# eGAN-FET-module_Driver.net
KiCad netlist of a schematic drawn in Altium Designer
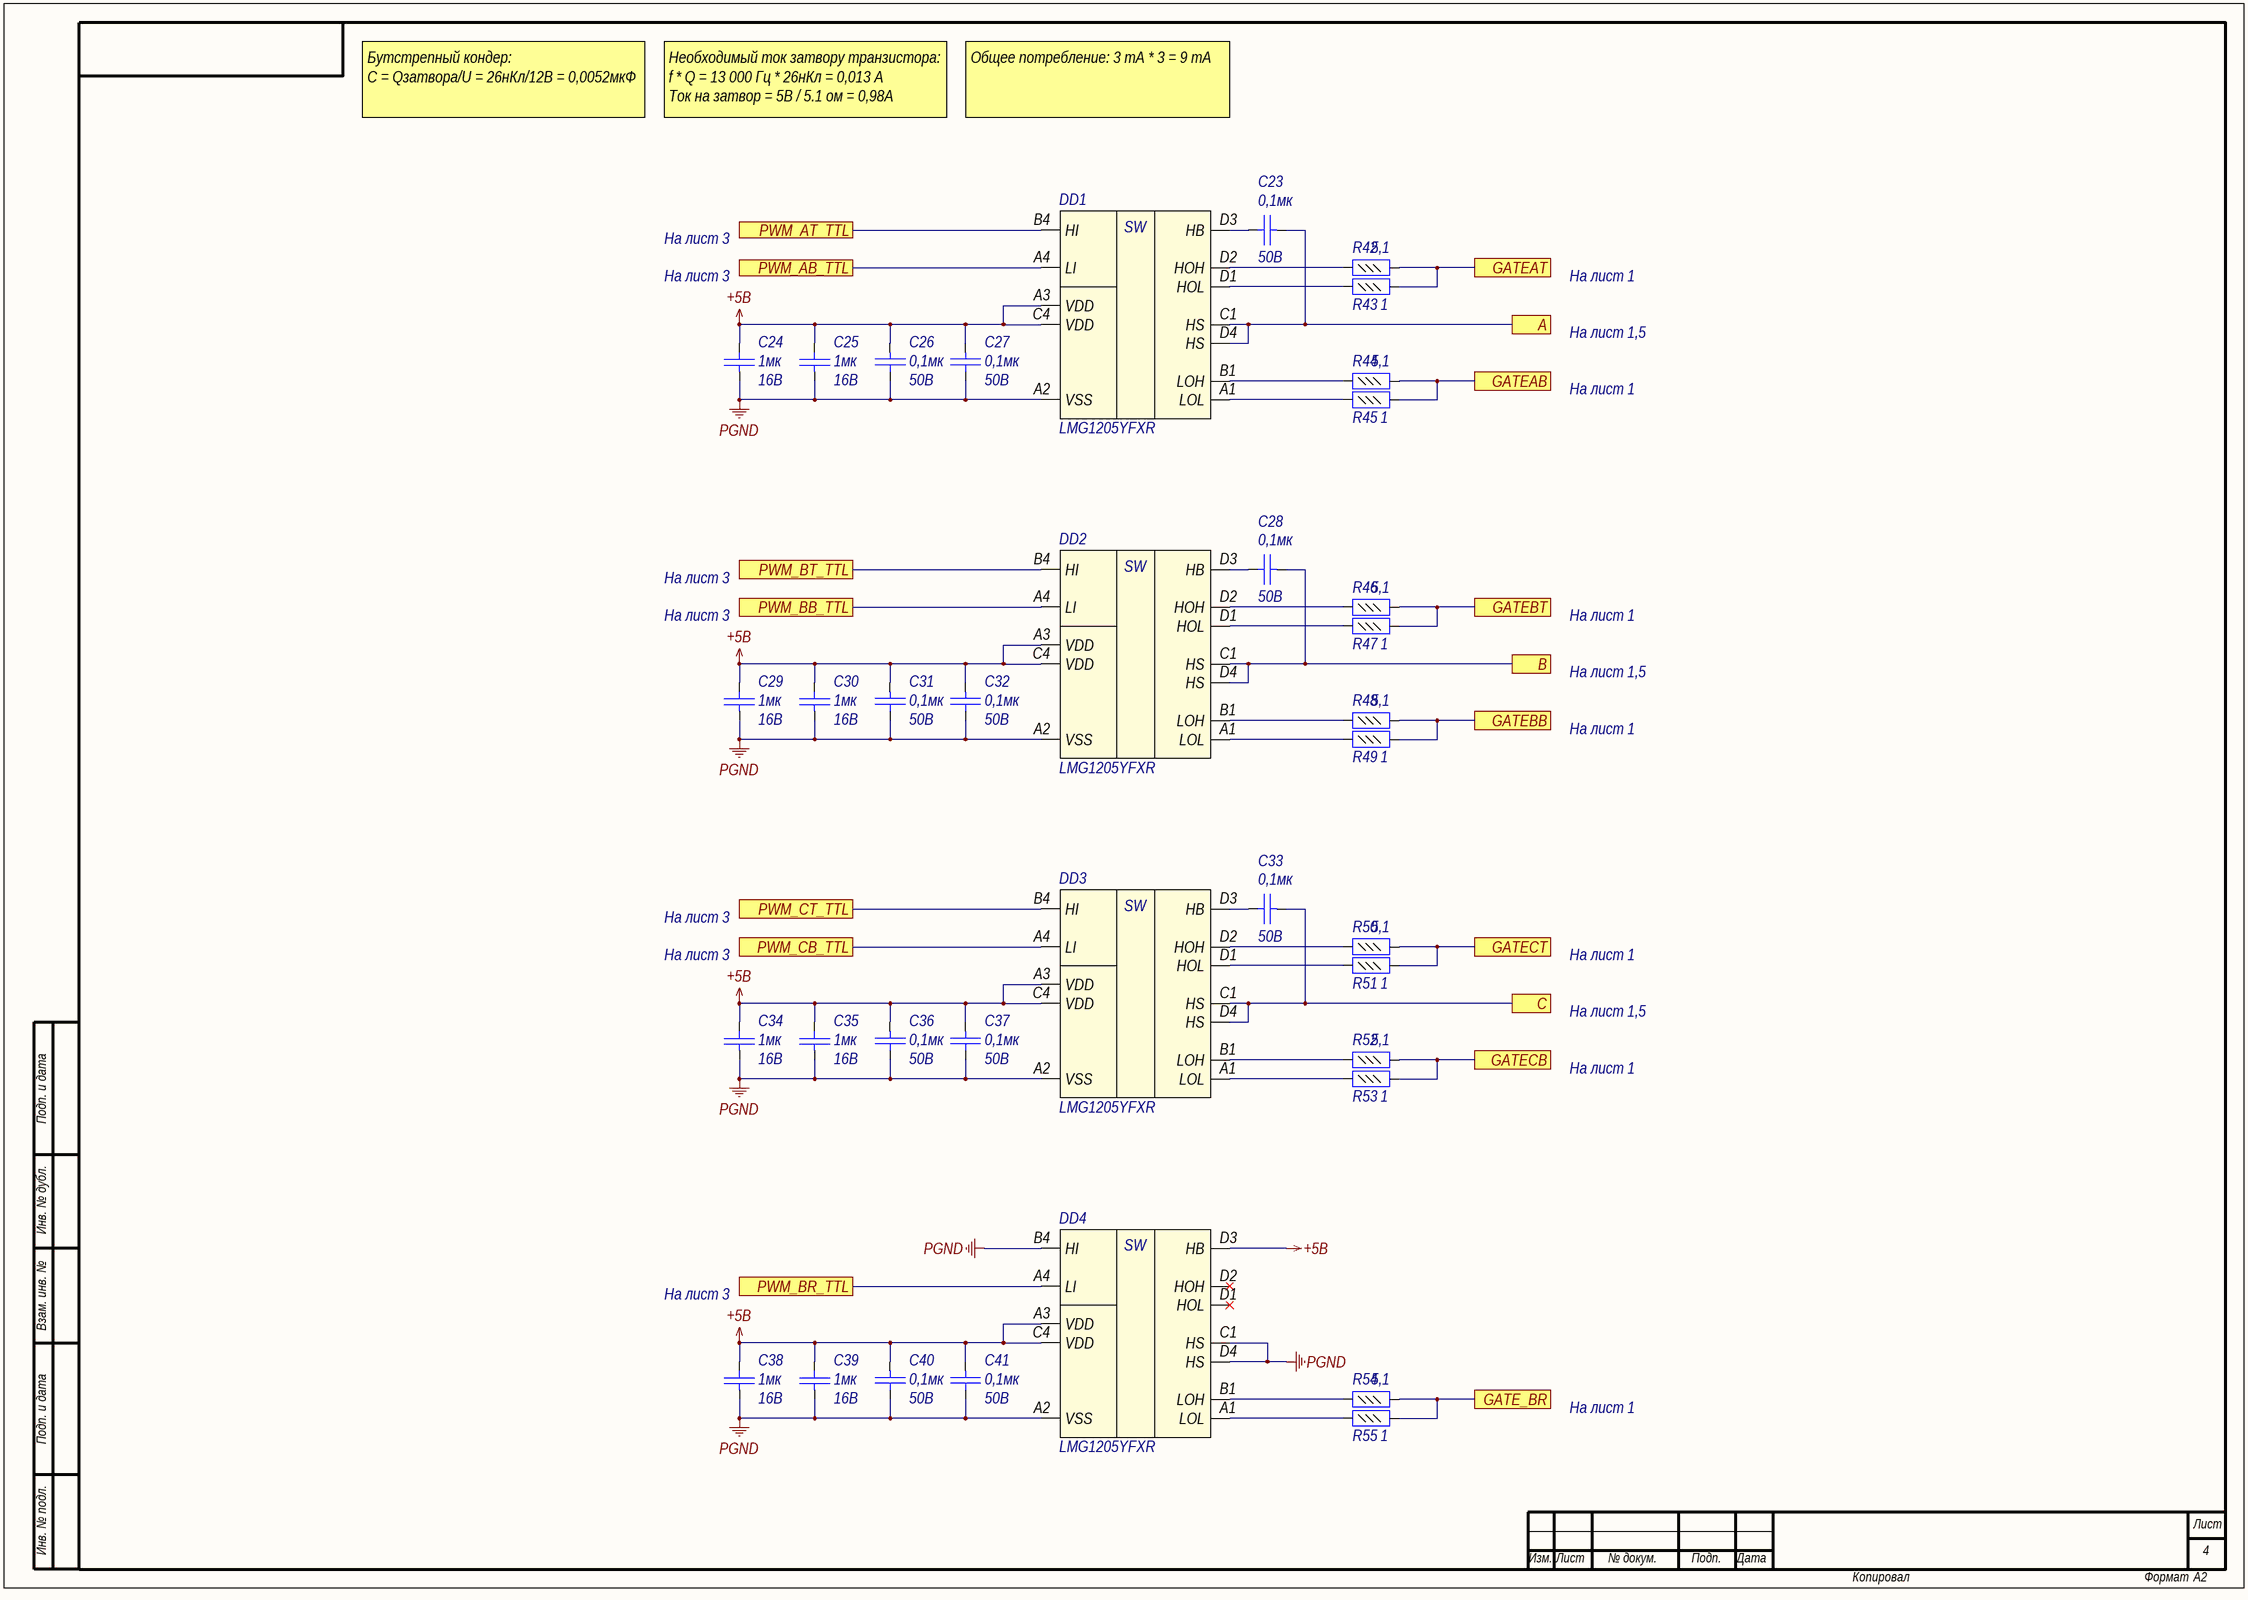
[diagram p0: eGAN-FET-module_Driver.SchDoc]

(export (version "E")
  (design (tool "Eeschema 10.0.6"))
  (components
    (comp (ref "C23")
      (value "0,1мк")
      (footprint "C0402")
      (description "Конденсатор")
      (fields
        (field (name "VOLTAGE") "50В")
        (field (name "PART NUMBER") "GRM155R71H104KE14D")
        (field (name "Comment") "Capacitor")
      )
      (libsource (lib "") (part "Capacitor_1"))
    )
    (comp (ref "C24")
      (value "1мк")
      (footprint "C0402")
      (description "Конденсатор")
      (fields (field (name "VOLTAGE") "16B") (field (name "PART NUMBER") "EMK105BJ105KV-F"))
      (libsource (lib "MOP44") (part "Capacitor"))
    )
    (comp (ref "C25")
      (value "1мк")
      (footprint "C0402")
      (description "Конденсатор")
      (fields (field (name "VOLTAGE") "16B") (field (name "PART NUMBER") "EMK105BJ105KV-F"))
      (libsource (lib "MOP44") (part "Capacitor"))
    )
    (comp (ref "C26")
      (value "0,1мк")
      (footprint "C0402")
      (description "Конденсатор")
      (fields
        (field (name "VOLTAGE") "50В")
        (field (name "PART NUMBER") "GRM155R71H104KE14D")
        (field (name "Comment") "Capacitor")
      )
      (libsource (lib "") (part "Capacitor_1"))
    )
    (comp (ref "C27")
      (value "0,1мк")
      (footprint "C0402")
      (description "Конденсатор")
      (fields
        (field (name "VOLTAGE") "50В")
        (field (name "PART NUMBER") "GRM155R71H104KE14D")
        (field (name "Comment") "Capacitor")
      )
      (libsource (lib "") (part "Capacitor_1"))
    )
    (comp (ref "C28")
      (value "0,1мк")
      (footprint "C0402")
      (description "Конденсатор")
      (fields
        (field (name "VOLTAGE") "50В")
        (field (name "PART NUMBER") "GRM155R71H104KE14D")
        (field (name "Comment") "Capacitor")
      )
      (libsource (lib "") (part "Capacitor_1"))
    )
    (comp (ref "C29")
      (value "1мк")
      (footprint "C0402")
      (description "Конденсатор")
      (fields (field (name "VOLTAGE") "16B") (field (name "PART NUMBER") "EMK105BJ105KV-F"))
      (libsource (lib "MOP44") (part "Capacitor"))
    )
    (comp (ref "C30")
      (value "1мк")
      (footprint "C0402")
      (description "Конденсатор")
      (fields (field (name "VOLTAGE") "16B") (field (name "PART NUMBER") "EMK105BJ105KV-F"))
      (libsource (lib "MOP44") (part "Capacitor"))
    )
    (comp (ref "C31")
      (value "0,1мк")
      (footprint "C0402")
      (description "Конденсатор")
      (fields
        (field (name "VOLTAGE") "50В")
        (field (name "PART NUMBER") "GRM155R71H104KE14D")
        (field (name "Comment") "Capacitor")
      )
      (libsource (lib "") (part "Capacitor_1"))
    )
    (comp (ref "C32")
      (value "0,1мк")
      (footprint "C0402")
      (description "Конденсатор")
      (fields
        (field (name "VOLTAGE") "50В")
        (field (name "PART NUMBER") "GRM155R71H104KE14D")
        (field (name "Comment") "Capacitor")
      )
      (libsource (lib "") (part "Capacitor_1"))
    )
    (comp (ref "C33")
      (value "0,1мк")
      (footprint "C0402")
      (description "Конденсатор")
      (fields
        (field (name "VOLTAGE") "50В")
        (field (name "PART NUMBER") "GRM155R71H104KE14D")
        (field (name "Comment") "Capacitor")
      )
      (libsource (lib "") (part "Capacitor_1"))
    )
    (comp (ref "C34")
      (value "1мк")
      (footprint "C0402")
      (description "Конденсатор")
      (fields (field (name "VOLTAGE") "16B") (field (name "PART NUMBER") "EMK105BJ105KV-F"))
      (libsource (lib "MOP44") (part "Capacitor"))
    )
    (comp (ref "C35")
      (value "1мк")
      (footprint "C0402")
      (description "Конденсатор")
      (fields (field (name "VOLTAGE") "16B") (field (name "PART NUMBER") "EMK105BJ105KV-F"))
      (libsource (lib "MOP44") (part "Capacitor"))
    )
    (comp (ref "C36")
      (value "0,1мк")
      (footprint "C0402")
      (description "Конденсатор")
      (fields
        (field (name "VOLTAGE") "50В")
        (field (name "PART NUMBER") "GRM155R71H104KE14D")
        (field (name "Comment") "Capacitor")
      )
      (libsource (lib "") (part "Capacitor_1"))
    )
    (comp (ref "C37")
      (value "0,1мк")
      (footprint "C0402")
      (description "Конденсатор")
      (fields
        (field (name "VOLTAGE") "50В")
        (field (name "PART NUMBER") "GRM155R71H104KE14D")
        (field (name "Comment") "Capacitor")
      )
      (libsource (lib "") (part "Capacitor_1"))
    )
    (comp (ref "C38")
      (value "1мк")
      (footprint "C0402")
      (description "Конденсатор")
      (fields (field (name "VOLTAGE") "16B") (field (name "PART NUMBER") "EMK105BJ105KV-F"))
      (libsource (lib "MOP44") (part "Capacitor"))
    )
    (comp (ref "C39")
      (value "1мк")
      (footprint "C0402")
      (description "Конденсатор")
      (fields (field (name "VOLTAGE") "16B") (field (name "PART NUMBER") "EMK105BJ105KV-F"))
      (libsource (lib "MOP44") (part "Capacitor"))
    )
    (comp (ref "C40")
      (value "0,1мк")
      (footprint "C0402")
      (description "Конденсатор")
      (fields
        (field (name "VOLTAGE") "50В")
        (field (name "PART NUMBER") "GRM155R71H104KE14D")
        (field (name "Comment") "Capacitor")
      )
      (libsource (lib "") (part "Capacitor_1"))
    )
    (comp (ref "C41")
      (value "0,1мк")
      (footprint "C0402")
      (description "Конденсатор")
      (fields
        (field (name "VOLTAGE") "50В")
        (field (name "PART NUMBER") "GRM155R71H104KE14D")
        (field (name "Comment") "Capacitor")
      )
      (libsource (lib "") (part "Capacitor_1"))
    )
    (comp (ref "DD1")
      (value "LMG1205YFXR")
      (footprint "DSBGA12")
      (description "80-V, 1.2-A to 5-A, Half Bridge GaN Driver with Integrated Bootstrap Diode")
      (libsource (lib "MOP44") (part "LMG1205"))
    )
    (comp (ref "DD2")
      (value "LMG1205YFXR")
      (footprint "DSBGA12")
      (description "80-V, 1.2-A to 5-A, Half Bridge GaN Driver with Integrated Bootstrap Diode")
      (libsource (lib "MOP44") (part "LMG1205"))
    )
    (comp (ref "DD3")
      (value "LMG1205YFXR")
      (footprint "DSBGA12")
      (description "80-V, 1.2-A to 5-A, Half Bridge GaN Driver with Integrated Bootstrap Diode")
      (libsource (lib "MOP44") (part "LMG1205"))
    )
    (comp (ref "DD4")
      (value "LMG1205YFXR")
      (footprint "DSBGA12")
      (description "80-V, 1.2-A to 5-A, Half Bridge GaN Driver with Integrated Bootstrap Diode")
      (libsource (lib "MOP44") (part "LMG1205"))
    )
    (comp (ref "R42")
      (value "5,1")
      (footprint "R0402")
      (description "Резистор")
      (fields (field (name "PART NUMBER") "RC0402FR-075R1L") (field (name "POWER") "0,062Вт"))
      (libsource (lib "MOP44") (part "Resistor_0,062Вт"))
    )
    (comp (ref "R43")
      (value "1")
      (footprint "R0402")
      (description "Резистор")
      (fields (field (name "PART NUMBER") "RC0402FR-071RL") (field (name "POWER") "0,062Вт"))
      (libsource (lib "MOP44") (part "Resistor_0,062Вт"))
    )
    (comp (ref "R44")
      (value "5,1")
      (footprint "R0402")
      (description "Резистор")
      (fields (field (name "PART NUMBER") "RC0402FR-075R1L") (field (name "POWER") "0,062Вт"))
      (libsource (lib "MOP44") (part "Resistor_0,062Вт"))
    )
    (comp (ref "R45")
      (value "1")
      (footprint "R0402")
      (description "Резистор")
      (fields (field (name "PART NUMBER") "RC0402FR-071RL") (field (name "POWER") "0,062Вт"))
      (libsource (lib "MOP44") (part "Resistor_0,062Вт"))
    )
    (comp (ref "R46")
      (value "5,1")
      (footprint "R0402")
      (description "Резистор")
      (fields (field (name "PART NUMBER") "RC0402FR-075R1L") (field (name "POWER") "0,062Вт"))
      (libsource (lib "MOP44") (part "Resistor_0,062Вт"))
    )
    (comp (ref "R47")
      (value "1")
      (footprint "R0402")
      (description "Резистор")
      (fields (field (name "PART NUMBER") "RC0402FR-071RL") (field (name "POWER") "0,062Вт"))
      (libsource (lib "MOP44") (part "Resistor_0,062Вт"))
    )
    (comp (ref "R48")
      (value "5,1")
      (footprint "R0402")
      (description "Резистор")
      (fields (field (name "PART NUMBER") "RC0402FR-075R1L") (field (name "POWER") "0,062Вт"))
      (libsource (lib "MOP44") (part "Resistor_0,062Вт"))
    )
    (comp (ref "R49")
      (value "1")
      (footprint "R0402")
      (description "Резистор")
      (fields (field (name "PART NUMBER") "RC0402FR-071RL") (field (name "POWER") "0,062Вт"))
      (libsource (lib "MOP44") (part "Resistor_0,062Вт"))
    )
    (comp (ref "R50")
      (value "5,1")
      (footprint "R0402")
      (description "Резистор")
      (fields (field (name "PART NUMBER") "RC0402FR-075R1L") (field (name "POWER") "0,062Вт"))
      (libsource (lib "MOP44") (part "Resistor_0,062Вт"))
    )
    (comp (ref "R51")
      (value "1")
      (footprint "R0402")
      (description "Резистор")
      (fields (field (name "PART NUMBER") "RC0402FR-071RL") (field (name "POWER") "0,062Вт"))
      (libsource (lib "MOP44") (part "Resistor_0,062Вт"))
    )
    (comp (ref "R52")
      (value "5,1")
      (footprint "R0402")
      (description "Резистор")
      (fields (field (name "PART NUMBER") "RC0402FR-075R1L") (field (name "POWER") "0,062Вт"))
      (libsource (lib "MOP44") (part "Resistor_0,062Вт"))
    )
    (comp (ref "R53")
      (value "1")
      (footprint "R0402")
      (description "Резистор")
      (fields (field (name "PART NUMBER") "RC0402FR-071RL") (field (name "POWER") "0,062Вт"))
      (libsource (lib "MOP44") (part "Resistor_0,062Вт"))
    )
    (comp (ref "R54")
      (value "5,1")
      (footprint "R0402")
      (description "Резистор")
      (fields (field (name "PART NUMBER") "RC0402FR-075R1L") (field (name "POWER") "0,062Вт"))
      (libsource (lib "MOP44") (part "Resistor_0,062Вт"))
    )
    (comp (ref "R55")
      (value "1")
      (footprint "R0402")
      (description "Резистор")
      (fields (field (name "PART NUMBER") "RC0402FR-071RL") (field (name "POWER") "0,062Вт"))
      (libsource (lib "MOP44") (part "Resistor_0,062Вт"))
    )
  )
  (nets
    (net (code "1") (name "+5B") (class "Default")
      (node (ref "C24") (pin "2") (pinfunction "2_2") (pintype "passive"))
      (node (ref "C25") (pin "2") (pinfunction "2_2") (pintype "passive"))
      (node (ref "C26") (pin "1") (pinfunction "1_1") (pintype "passive"))
      (node (ref "C27") (pin "1") (pinfunction "1_1") (pintype "passive"))
      (node (ref "C29") (pin "2") (pinfunction "2_2") (pintype "passive"))
      (node (ref "C30") (pin "2") (pinfunction "2_2") (pintype "passive"))
      (node (ref "C31") (pin "1") (pinfunction "1_1") (pintype "passive"))
      (node (ref "C32") (pin "1") (pinfunction "1_1") (pintype "passive"))
      (node (ref "C34") (pin "2") (pinfunction "2_2") (pintype "passive"))
      (node (ref "C35") (pin "2") (pinfunction "2_2") (pintype "passive"))
      (node (ref "C36") (pin "1") (pinfunction "1_1") (pintype "passive"))
      (node (ref "C37") (pin "1") (pinfunction "1_1") (pintype "passive"))
      (node (ref "C38") (pin "2") (pinfunction "2_2") (pintype "passive"))
      (node (ref "C39") (pin "2") (pinfunction "2_2") (pintype "passive"))
      (node (ref "C40") (pin "1") (pinfunction "1_1") (pintype "passive"))
      (node (ref "C41") (pin "1") (pinfunction "1_1") (pintype "passive"))
      (node (ref "DD1") (pin "A3") (pinfunction "VDD_A3") (pintype "passive"))
      (node (ref "DD1") (pin "C4") (pinfunction "VDD_C4") (pintype "passive"))
      (node (ref "DD2") (pin "A3") (pinfunction "VDD_A3") (pintype "passive"))
      (node (ref "DD2") (pin "C4") (pinfunction "VDD_C4") (pintype "passive"))
      (node (ref "DD3") (pin "A3") (pinfunction "VDD_A3") (pintype "passive"))
      (node (ref "DD3") (pin "C4") (pinfunction "VDD_C4") (pintype "passive"))
      (node (ref "DD4") (pin "A3") (pinfunction "VDD_A3") (pintype "passive"))
      (node (ref "DD4") (pin "C4") (pinfunction "VDD_C4") (pintype "passive"))
      (node (ref "DD4") (pin "D3") (pinfunction "HB_D3") (pintype "passive"))
    )
    (net (code "2") (name "/A") (class "Default")
      (node (ref "C23") (pin "1") (pinfunction "1_1") (pintype "passive"))
      (node (ref "DD1") (pin "C1") (pinfunction "HS_C1") (pintype "passive"))
      (node (ref "DD1") (pin "D4") (pinfunction "HS_D4") (pintype "passive"))
    )
    (net (code "3") (name "/B") (class "Default")
      (node (ref "C28") (pin "1") (pinfunction "1_1") (pintype "passive"))
      (node (ref "DD2") (pin "C1") (pinfunction "HS_C1") (pintype "passive"))
      (node (ref "DD2") (pin "D4") (pinfunction "HS_D4") (pintype "passive"))
    )
    (net (code "4") (name "/C") (class "Default")
      (node (ref "C33") (pin "1") (pinfunction "1_1") (pintype "passive"))
      (node (ref "DD3") (pin "C1") (pinfunction "HS_C1") (pintype "passive"))
      (node (ref "DD3") (pin "D4") (pinfunction "HS_D4") (pintype "passive"))
    )
    (net (code "5") (name "/GATEAB") (class "Default")
      (node (ref "R44") (pin "2") (pinfunction "2_2") (pintype "passive"))
      (node (ref "R45") (pin "2") (pinfunction "2_2") (pintype "passive"))
    )
    (net (code "6") (name "/GATEAT") (class "Default")
      (node (ref "R42") (pin "2") (pinfunction "2_2") (pintype "passive"))
      (node (ref "R43") (pin "2") (pinfunction "2_2") (pintype "passive"))
    )
    (net (code "7") (name "/GATEBB") (class "Default")
      (node (ref "R48") (pin "2") (pinfunction "2_2") (pintype "passive"))
      (node (ref "R49") (pin "2") (pinfunction "2_2") (pintype "passive"))
    )
    (net (code "8") (name "/GATEBT") (class "Default")
      (node (ref "R46") (pin "2") (pinfunction "2_2") (pintype "passive"))
      (node (ref "R47") (pin "2") (pinfunction "2_2") (pintype "passive"))
    )
    (net (code "9") (name "/GATECB") (class "Default")
      (node (ref "R52") (pin "2") (pinfunction "2_2") (pintype "passive"))
      (node (ref "R53") (pin "2") (pinfunction "2_2") (pintype "passive"))
    )
    (net (code "10") (name "/GATECT") (class "Default")
      (node (ref "R50") (pin "2") (pinfunction "2_2") (pintype "passive"))
      (node (ref "R51") (pin "2") (pinfunction "2_2") (pintype "passive"))
    )
    (net (code "11") (name "/GATE_BR") (class "Default")
      (node (ref "R54") (pin "2") (pinfunction "2_2") (pintype "passive"))
      (node (ref "R55") (pin "2") (pinfunction "2_2") (pintype "passive"))
    )
    (net (code "12") (name "/PWM_AB_TTL") (class "Default")
      (node (ref "DD1") (pin "A4") (pinfunction "LI_A4") (pintype "passive"))
    )
    (net (code "13") (name "/PWM_AT_TTL") (class "Default")
      (node (ref "DD1") (pin "B4") (pinfunction "HI_B4") (pintype "passive"))
    )
    (net (code "14") (name "/PWM_BB_TTL") (class "Default")
      (node (ref "DD2") (pin "A4") (pinfunction "LI_A4") (pintype "passive"))
    )
    (net (code "15") (name "/PWM_BR_TTL") (class "Default")
      (node (ref "DD4") (pin "A4") (pinfunction "LI_A4") (pintype "passive"))
    )
    (net (code "16") (name "/PWM_BT_TTL") (class "Default")
      (node (ref "DD2") (pin "B4") (pinfunction "HI_B4") (pintype "passive"))
    )
    (net (code "17") (name "/PWM_CB_TTL") (class "Default")
      (node (ref "DD3") (pin "A4") (pinfunction "LI_A4") (pintype "passive"))
    )
    (net (code "18") (name "/PWM_CT_TTL") (class "Default")
      (node (ref "DD3") (pin "B4") (pinfunction "HI_B4") (pintype "passive"))
    )
    (net (code "19") (name "Net-(DD1-HB)") (class "Default")
      (node (ref "C23") (pin "2") (pinfunction "2_2") (pintype "passive"))
      (node (ref "DD1") (pin "D3") (pinfunction "HB_D3") (pintype "passive"))
    )
    (net (code "20") (name "Net-(DD1-HOH)") (class "Default")
      (node (ref "DD1") (pin "D2") (pinfunction "HOH_D2") (pintype "passive"))
      (node (ref "R42") (pin "1") (pinfunction "1_1") (pintype "passive"))
    )
    (net (code "21") (name "Net-(DD1-HOL)") (class "Default")
      (node (ref "DD1") (pin "D1") (pinfunction "HOL_D1") (pintype "passive"))
      (node (ref "R43") (pin "1") (pinfunction "1_1") (pintype "passive"))
    )
    (net (code "22") (name "Net-(DD1-LOH)") (class "Default")
      (node (ref "DD1") (pin "B1") (pinfunction "LOH_B1") (pintype "passive"))
      (node (ref "R44") (pin "1") (pinfunction "1_1") (pintype "passive"))
    )
    (net (code "23") (name "Net-(DD1-LOL)") (class "Default")
      (node (ref "DD1") (pin "A1") (pinfunction "LOL_A1") (pintype "passive"))
      (node (ref "R45") (pin "1") (pinfunction "1_1") (pintype "passive"))
    )
    (net (code "24") (name "Net-(DD2-HB)") (class "Default")
      (node (ref "C28") (pin "2") (pinfunction "2_2") (pintype "passive"))
      (node (ref "DD2") (pin "D3") (pinfunction "HB_D3") (pintype "passive"))
    )
    (net (code "25") (name "Net-(DD2-HOH)") (class "Default")
      (node (ref "DD2") (pin "D2") (pinfunction "HOH_D2") (pintype "passive"))
      (node (ref "R46") (pin "1") (pinfunction "1_1") (pintype "passive"))
    )
    (net (code "26") (name "Net-(DD2-HOL)") (class "Default")
      (node (ref "DD2") (pin "D1") (pinfunction "HOL_D1") (pintype "passive"))
      (node (ref "R47") (pin "1") (pinfunction "1_1") (pintype "passive"))
    )
    (net (code "27") (name "Net-(DD2-LOH)") (class "Default")
      (node (ref "DD2") (pin "B1") (pinfunction "LOH_B1") (pintype "passive"))
      (node (ref "R48") (pin "1") (pinfunction "1_1") (pintype "passive"))
    )
    (net (code "28") (name "Net-(DD2-LOL)") (class "Default")
      (node (ref "DD2") (pin "A1") (pinfunction "LOL_A1") (pintype "passive"))
      (node (ref "R49") (pin "1") (pinfunction "1_1") (pintype "passive"))
    )
    (net (code "29") (name "Net-(DD3-HB)") (class "Default")
      (node (ref "C33") (pin "2") (pinfunction "2_2") (pintype "passive"))
      (node (ref "DD3") (pin "D3") (pinfunction "HB_D3") (pintype "passive"))
    )
    (net (code "30") (name "Net-(DD3-HOH)") (class "Default")
      (node (ref "DD3") (pin "D2") (pinfunction "HOH_D2") (pintype "passive"))
      (node (ref "R50") (pin "1") (pinfunction "1_1") (pintype "passive"))
    )
    (net (code "31") (name "Net-(DD3-HOL)") (class "Default")
      (node (ref "DD3") (pin "D1") (pinfunction "HOL_D1") (pintype "passive"))
      (node (ref "R51") (pin "1") (pinfunction "1_1") (pintype "passive"))
    )
    (net (code "32") (name "Net-(DD3-LOH)") (class "Default")
      (node (ref "DD3") (pin "B1") (pinfunction "LOH_B1") (pintype "passive"))
      (node (ref "R52") (pin "1") (pinfunction "1_1") (pintype "passive"))
    )
    (net (code "33") (name "Net-(DD3-LOL)") (class "Default")
      (node (ref "DD3") (pin "A1") (pinfunction "LOL_A1") (pintype "passive"))
      (node (ref "R53") (pin "1") (pinfunction "1_1") (pintype "passive"))
    )
    (net (code "34") (name "Net-(DD4-LOH)") (class "Default")
      (node (ref "DD4") (pin "B1") (pinfunction "LOH_B1") (pintype "passive"))
      (node (ref "R54") (pin "1") (pinfunction "1_1") (pintype "passive"))
    )
    (net (code "35") (name "Net-(DD4-LOL)") (class "Default")
      (node (ref "DD4") (pin "A1") (pinfunction "LOL_A1") (pintype "passive"))
      (node (ref "R55") (pin "1") (pinfunction "1_1") (pintype "passive"))
    )
    (net (code "36") (name "PGND") (class "Default")
      (node (ref "C24") (pin "1") (pinfunction "1_1") (pintype "passive"))
      (node (ref "C25") (pin "1") (pinfunction "1_1") (pintype "passive"))
      (node (ref "C26") (pin "2") (pinfunction "2_2") (pintype "passive"))
      (node (ref "C27") (pin "2") (pinfunction "2_2") (pintype "passive"))
      (node (ref "C29") (pin "1") (pinfunction "1_1") (pintype "passive"))
      (node (ref "C30") (pin "1") (pinfunction "1_1") (pintype "passive"))
      (node (ref "C31") (pin "2") (pinfunction "2_2") (pintype "passive"))
      (node (ref "C32") (pin "2") (pinfunction "2_2") (pintype "passive"))
      (node (ref "C34") (pin "1") (pinfunction "1_1") (pintype "passive"))
      (node (ref "C35") (pin "1") (pinfunction "1_1") (pintype "passive"))
      (node (ref "C36") (pin "2") (pinfunction "2_2") (pintype "passive"))
      (node (ref "C37") (pin "2") (pinfunction "2_2") (pintype "passive"))
      (node (ref "C38") (pin "1") (pinfunction "1_1") (pintype "passive"))
      (node (ref "C39") (pin "1") (pinfunction "1_1") (pintype "passive"))
      (node (ref "C40") (pin "2") (pinfunction "2_2") (pintype "passive"))
      (node (ref "C41") (pin "2") (pinfunction "2_2") (pintype "passive"))
      (node (ref "DD1") (pin "A2") (pinfunction "VSS_A2") (pintype "passive"))
      (node (ref "DD2") (pin "A2") (pinfunction "VSS_A2") (pintype "passive"))
      (node (ref "DD3") (pin "A2") (pinfunction "VSS_A2") (pintype "passive"))
      (node (ref "DD4") (pin "A2") (pinfunction "VSS_A2") (pintype "passive"))
      (node (ref "DD4") (pin "B4") (pinfunction "HI_B4") (pintype "passive"))
      (node (ref "DD4") (pin "C1") (pinfunction "HS_C1") (pintype "passive"))
      (node (ref "DD4") (pin "D4") (pinfunction "HS_D4") (pintype "passive"))
    )
    (net (code "37") (name "unconnected-(DD4-HOH-PadD2)") (class "Default")
      (node (ref "DD4") (pin "D2") (pinfunction "HOH_D2") (pintype "passive+no_connect"))
    )
    (net (code "38") (name "unconnected-(DD4-HOL-PadD1)") (class "Default")
      (node (ref "DD4") (pin "D1") (pinfunction "HOL_D1") (pintype "passive+no_connect"))
    )
  )
)
